# 08_BB_Processor.net
KiCad netlist of a schematic drawn in Altium Designer
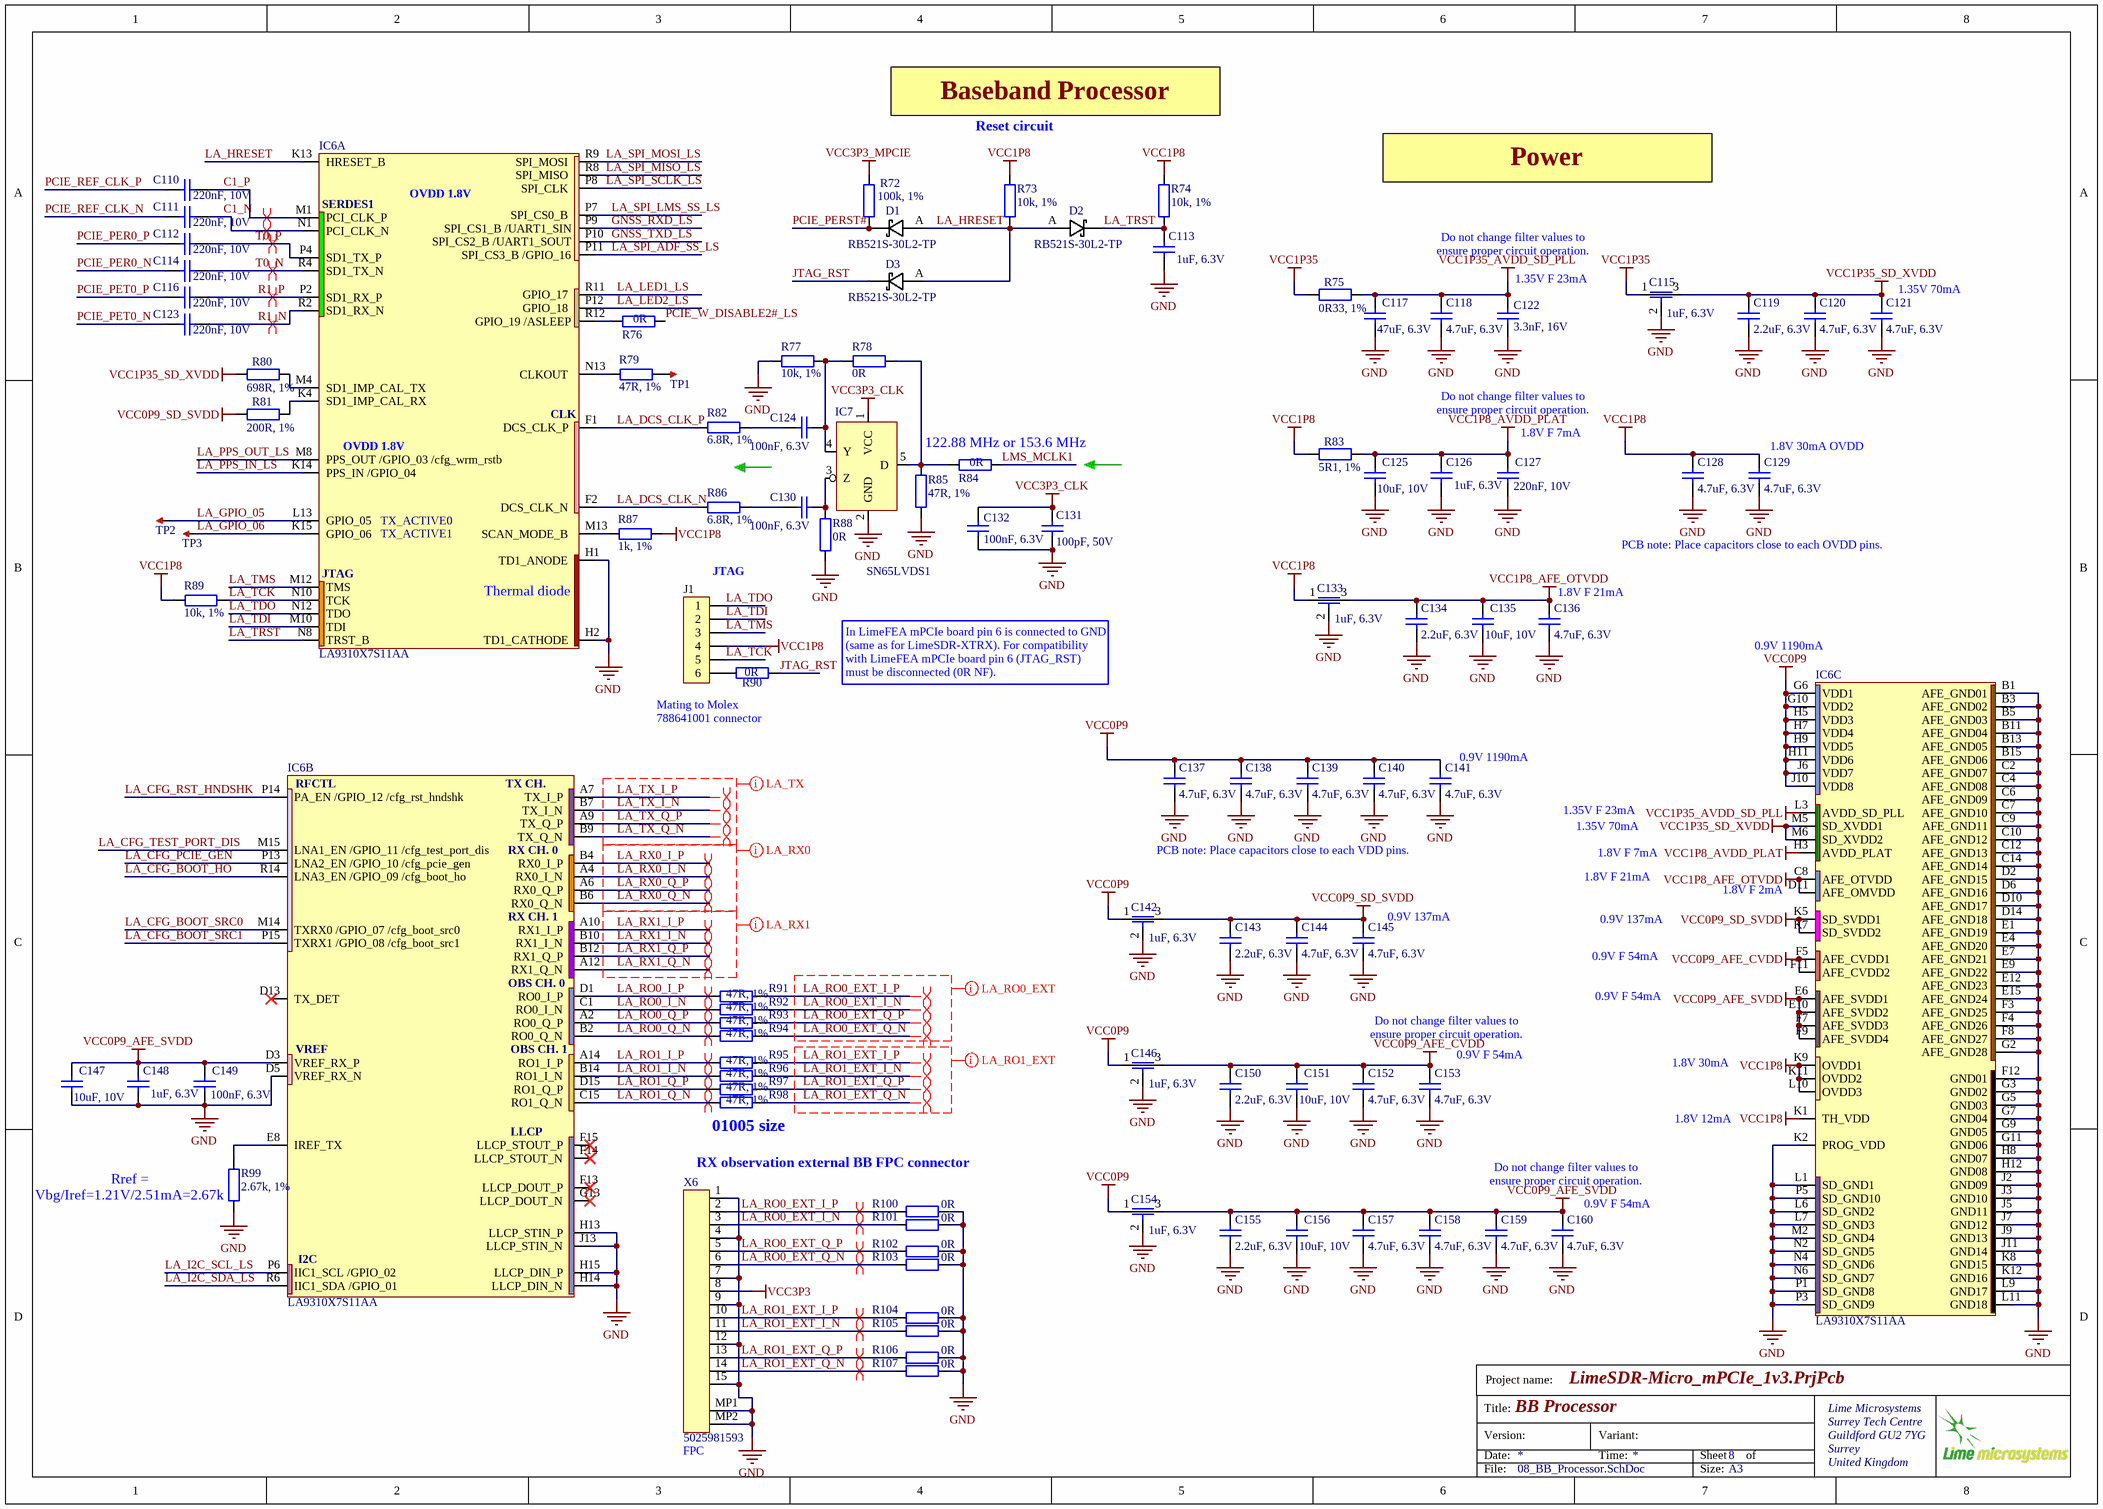
[diagram p0: 08_BB_Processor.SchDoc]

(export (version "E")
  (design (tool "Eeschema 10.0.6"))
  (components
    (comp (ref "C110")
      (value "220nF, 10V")
      (footprint "CAP0201")
      (fields
        (field (name "MANUFACTURER") "Murata")
        (field (name "TOLERANCE") "20%")
        (field (name "VOLTAGE") "10V")
      )
      (libsource (lib "LimeMicroAltiumLib_schLib") (part "Cap_0402"))
    )
    (comp (ref "C111")
      (value "220nF, 10V")
      (footprint "CAP0201")
      (fields
        (field (name "MANUFACTURER") "Murata")
        (field (name "TOLERANCE") "20%")
        (field (name "VOLTAGE") "10V")
      )
      (libsource (lib "LimeMicroAltiumLib_schLib") (part "Cap_0402"))
    )
    (comp (ref "C112")
      (value "220nF, 10V")
      (footprint "CAP0201")
      (fields
        (field (name "MANUFACTURER") "Murata")
        (field (name "TOLERANCE") "20%")
        (field (name "VOLTAGE") "10V")
      )
      (libsource (lib "LimeMicroAltiumLib_schLib") (part "Cap_0402"))
    )
    (comp (ref "C113")
      (value "1uF, 6.3V")
      (footprint "CAP0201")
      (fields (field (name "TOLERANCE") "±20%") (field (name "MANUFACTURER") "TDK Corporation"))
      (libsource (lib "LimeMicroAltiumLib_schLib") (part "Cap_0402"))
    )
    (comp (ref "C114")
      (value "220nF, 10V")
      (footprint "CAP0201")
      (fields
        (field (name "MANUFACTURER") "Murata")
        (field (name "TOLERANCE") "20%")
        (field (name "VOLTAGE") "10V")
      )
      (libsource (lib "LimeMicroAltiumLib_schLib") (part "Cap_0402"))
    )
    (comp (ref "C115")
      (value "1uF, 6.3V")
      (footprint "CAP0603_FEEDTHROUGH")
      (fields (field (name "MANUFACTURER") "TDK"))
      (libsource (lib "LimeMicroAltiumLib_schLib_r01") (part "Cap_feed_through"))
    )
    (comp (ref "C116")
      (value "220nF, 10V")
      (footprint "CAP0201")
      (fields
        (field (name "MANUFACTURER") "Murata")
        (field (name "TOLERANCE") "20%")
        (field (name "VOLTAGE") "10V")
      )
      (libsource (lib "LimeMicroAltiumLib_schLib") (part "Cap_0402"))
    )
    (comp (ref "C117")
      (value "47uF, 6.3V")
      (footprint "CAP0603")
      (fields (field (name "MANUFACTURER") "Murata") (field (name "TOLERANCE") "20%"))
      (libsource (lib "LimeFPGAboard_schLib") (part "Cap_0603"))
    )
    (comp (ref "C118")
      (value "4.7uF, 6.3V")
      (footprint "CAP0201")
      (fields (field (name "MANUFACTURER") "Murata") (field (name "TOLERANCE") "20%"))
      (libsource (lib "LimeMicroAltiumLib_schLib") (part "Cap_0402"))
    )
    (comp (ref "C119")
      (value "2.2uF, 6.3V")
      (footprint "CAP0201")
      (fields (field (name "MANUFACTURER") "Murata") (field (name "TOLERANCE") "20%"))
      (libsource (lib "LimeMicroAltiumLib_schLib") (part "Cap_0402"))
    )
    (comp (ref "C120")
      (value "4.7uF, 6.3V")
      (footprint "CAP0201")
      (fields (field (name "MANUFACTURER") "Murata") (field (name "TOLERANCE") "20%"))
      (libsource (lib "LimeMicroAltiumLib_schLib") (part "Cap_0402"))
    )
    (comp (ref "C121")
      (value "4.7uF, 6.3V")
      (footprint "CAP0201")
      (fields (field (name "MANUFACTURER") "Murata") (field (name "TOLERANCE") "20%"))
      (libsource (lib "LimeMicroAltiumLib_schLib") (part "Cap_0402"))
    )
    (comp (ref "C122")
      (value "3.3nF, 16V")
      (footprint "CAP0201")
      (fields (field (name "MANUFACTURER") "Murata"))
      (libsource (lib "LimeMicroAltiumLib_schLib") (part "Cap_0402"))
    )
    (comp (ref "C123")
      (value "220nF, 10V")
      (footprint "CAP0201")
      (fields
        (field (name "MANUFACTURER") "Murata")
        (field (name "TOLERANCE") "20%")
        (field (name "VOLTAGE") "10V")
      )
      (libsource (lib "LimeMicroAltiumLib_schLib") (part "Cap_0402"))
    )
    (comp (ref "C124")
      (value "100nF, 6.3V")
      (footprint "CAP0201")
      (fields (field (name "MANUFACTURER") "Samsung") (field (name "TOLERANCE") "20%"))
      (libsource (lib "LimeMicroAltiumLib_schLib") (part "Cap_0402"))
    )
    (comp (ref "C125")
      (value "10uF, 10V")
      (footprint "CAP0402")
      (fields (field (name "MANUFACTURER") "Murata"))
      (libsource (lib "LimeFPGAboard_schLib") (part "Cap_0603"))
    )
    (comp (ref "C126")
      (value "1uF, 6.3V")
      (footprint "CAP0201")
      (fields (field (name "TOLERANCE") "±20%") (field (name "MANUFACTURER") "TDK Corporation"))
      (libsource (lib "LimeMicroAltiumLib_schLib") (part "Cap_0402"))
    )
    (comp (ref "C127")
      (value "220nF, 10V")
      (footprint "CAP0201")
      (fields
        (field (name "MANUFACTURER") "Murata")
        (field (name "TOLERANCE") "20%")
        (field (name "VOLTAGE") "10V")
      )
      (libsource (lib "LimeMicroAltiumLib_schLib") (part "Cap_0402"))
    )
    (comp (ref "C128")
      (value "4.7uF, 6.3V")
      (footprint "CAP0201")
      (fields (field (name "MANUFACTURER") "Murata") (field (name "TOLERANCE") "20%"))
      (libsource (lib "LimeMicroAltiumLib_schLib") (part "Cap_0402"))
    )
    (comp (ref "C129")
      (value "4.7uF, 6.3V")
      (footprint "CAP0201")
      (fields (field (name "MANUFACTURER") "Murata") (field (name "TOLERANCE") "20%"))
      (libsource (lib "LimeMicroAltiumLib_schLib") (part "Cap_0402"))
    )
    (comp (ref "C130")
      (value "100nF, 6.3V")
      (footprint "CAP0201")
      (fields (field (name "MANUFACTURER") "Samsung") (field (name "TOLERANCE") "20%"))
      (libsource (lib "LimeMicroAltiumLib_schLib") (part "Cap_0402"))
    )
    (comp (ref "C131")
      (value "100pF, 50V")
      (footprint "CAP0201")
      (fields
        (field (name "MANUFACTURER") "TDK")
        (field (name "TOLERANCE") "5%")
        (field (name "VOLTAGE") "50V")
      )
      (libsource (lib "LimeMicroAltiumLib_schLib") (part "Cap_0402"))
    )
    (comp (ref "C132")
      (value "100nF, 6.3V")
      (footprint "CAP0201")
      (fields (field (name "MANUFACTURER") "Samsung") (field (name "TOLERANCE") "20%"))
      (libsource (lib "LimeMicroAltiumLib_schLib") (part "Cap_0402"))
    )
    (comp (ref "C133")
      (value "1uF, 6.3V")
      (footprint "CAP0603_FEEDTHROUGH")
      (fields (field (name "MANUFACTURER") "TDK"))
      (libsource (lib "LimeMicroAltiumLib_schLib_r01") (part "Cap_feed_through"))
    )
    (comp (ref "C134")
      (value "2.2uF, 6.3V")
      (footprint "CAP0201")
      (fields (field (name "MANUFACTURER") "Murata") (field (name "TOLERANCE") "20%"))
      (libsource (lib "LimeMicroAltiumLib_schLib") (part "Cap_0402"))
    )
    (comp (ref "C135")
      (value "10uF, 10V")
      (footprint "CAP0402")
      (fields (field (name "MANUFACTURER") "Murata"))
      (libsource (lib "LimeFPGAboard_schLib") (part "Cap_0603"))
    )
    (comp (ref "C136")
      (value "4.7uF, 6.3V")
      (footprint "CAP0201")
      (fields (field (name "MANUFACTURER") "Murata") (field (name "TOLERANCE") "20%"))
      (libsource (lib "LimeMicroAltiumLib_schLib") (part "Cap_0402"))
    )
    (comp (ref "C137")
      (value "4.7uF, 6.3V")
      (footprint "CAP0201")
      (fields (field (name "MANUFACTURER") "Murata") (field (name "TOLERANCE") "20%"))
      (libsource (lib "LimeMicroAltiumLib_schLib") (part "Cap_0402"))
    )
    (comp (ref "C138")
      (value "4.7uF, 6.3V")
      (footprint "CAP0201")
      (fields (field (name "MANUFACTURER") "Murata") (field (name "TOLERANCE") "20%"))
      (libsource (lib "LimeMicroAltiumLib_schLib") (part "Cap_0402"))
    )
    (comp (ref "C139")
      (value "4.7uF, 6.3V")
      (footprint "CAP0201")
      (fields (field (name "MANUFACTURER") "Murata") (field (name "TOLERANCE") "20%"))
      (libsource (lib "LimeMicroAltiumLib_schLib") (part "Cap_0402"))
    )
    (comp (ref "C140")
      (value "4.7uF, 6.3V")
      (footprint "CAP0201")
      (fields (field (name "MANUFACTURER") "Murata") (field (name "TOLERANCE") "20%"))
      (libsource (lib "LimeMicroAltiumLib_schLib") (part "Cap_0402"))
    )
    (comp (ref "C141")
      (value "4.7uF, 6.3V")
      (footprint "CAP0201")
      (fields (field (name "MANUFACTURER") "Murata") (field (name "TOLERANCE") "20%"))
      (libsource (lib "LimeMicroAltiumLib_schLib") (part "Cap_0402"))
    )
    (comp (ref "C142")
      (value "1uF, 6.3V")
      (footprint "CAP0603_FEEDTHROUGH")
      (fields (field (name "MANUFACTURER") "TDK"))
      (libsource (lib "LimeMicroAltiumLib_schLib_r01") (part "Cap_feed_through"))
    )
    (comp (ref "C143")
      (value "2.2uF, 6.3V")
      (footprint "CAP0201")
      (fields (field (name "MANUFACTURER") "Murata") (field (name "TOLERANCE") "20%"))
      (libsource (lib "LimeMicroAltiumLib_schLib") (part "Cap_0402"))
    )
    (comp (ref "C144")
      (value "4.7uF, 6.3V")
      (footprint "CAP0201")
      (fields (field (name "MANUFACTURER") "Murata") (field (name "TOLERANCE") "20%"))
      (libsource (lib "LimeMicroAltiumLib_schLib") (part "Cap_0402"))
    )
    (comp (ref "C145")
      (value "4.7uF, 6.3V")
      (footprint "CAP0201")
      (fields (field (name "MANUFACTURER") "Murata") (field (name "TOLERANCE") "20%"))
      (libsource (lib "LimeMicroAltiumLib_schLib") (part "Cap_0402"))
    )
    (comp (ref "C146")
      (value "1uF, 6.3V")
      (footprint "CAP0603_FEEDTHROUGH")
      (fields (field (name "MANUFACTURER") "TDK"))
      (libsource (lib "LimeMicroAltiumLib_schLib_r01") (part "Cap_feed_through"))
    )
    (comp (ref "C147")
      (value "10uF, 10V")
      (footprint "CAP0402")
      (fields (field (name "MANUFACTURER") "Murata"))
      (libsource (lib "LimeFPGAboard_schLib") (part "Cap_0603"))
    )
    (comp (ref "C148")
      (value "1uF, 6.3V")
      (footprint "CAP0201")
      (fields (field (name "TOLERANCE") "±20%") (field (name "MANUFACTURER") "TDK Corporation"))
      (libsource (lib "LimeMicroAltiumLib_schLib") (part "Cap_0402"))
    )
    (comp (ref "C149")
      (value "100nF, 6.3V")
      (footprint "CAP0201")
      (fields (field (name "MANUFACTURER") "Samsung") (field (name "TOLERANCE") "20%"))
      (libsource (lib "LimeMicroAltiumLib_schLib") (part "Cap_0402"))
    )
    (comp (ref "C150")
      (value "2.2uF, 6.3V")
      (footprint "CAP0201")
      (fields (field (name "MANUFACTURER") "Murata") (field (name "TOLERANCE") "20%"))
      (libsource (lib "LimeMicroAltiumLib_schLib") (part "Cap_0402"))
    )
    (comp (ref "C151")
      (value "10uF, 10V")
      (footprint "CAP0402")
      (fields (field (name "MANUFACTURER") "Murata"))
      (libsource (lib "LimeFPGAboard_schLib") (part "Cap_0603"))
    )
    (comp (ref "C152")
      (value "4.7uF, 6.3V")
      (footprint "CAP0201")
      (fields (field (name "MANUFACTURER") "Murata") (field (name "TOLERANCE") "20%"))
      (libsource (lib "LimeMicroAltiumLib_schLib") (part "Cap_0402"))
    )
    (comp (ref "C153")
      (value "4.7uF, 6.3V")
      (footprint "CAP0201")
      (fields (field (name "MANUFACTURER") "Murata") (field (name "TOLERANCE") "20%"))
      (libsource (lib "LimeMicroAltiumLib_schLib") (part "Cap_0402"))
    )
    (comp (ref "C154")
      (value "1uF, 6.3V")
      (footprint "CAP0603_FEEDTHROUGH")
      (fields (field (name "MANUFACTURER") "TDK"))
      (libsource (lib "LimeMicroAltiumLib_schLib_r01") (part "Cap_feed_through"))
    )
    (comp (ref "C155")
      (value "2.2uF, 6.3V")
      (footprint "CAP0201")
      (fields (field (name "MANUFACTURER") "Murata") (field (name "TOLERANCE") "20%"))
      (libsource (lib "LimeMicroAltiumLib_schLib") (part "Cap_0402"))
    )
    (comp (ref "C156")
      (value "10uF, 10V")
      (footprint "CAP0402")
      (fields (field (name "MANUFACTURER") "Murata"))
      (libsource (lib "LimeFPGAboard_schLib") (part "Cap_0603"))
    )
    (comp (ref "C157")
      (value "4.7uF, 6.3V")
      (footprint "CAP0201")
      (fields (field (name "MANUFACTURER") "Murata") (field (name "TOLERANCE") "20%"))
      (libsource (lib "LimeMicroAltiumLib_schLib") (part "Cap_0402"))
    )
    (comp (ref "C158")
      (value "4.7uF, 6.3V")
      (footprint "CAP0201")
      (fields (field (name "MANUFACTURER") "Murata") (field (name "TOLERANCE") "20%"))
      (libsource (lib "LimeMicroAltiumLib_schLib") (part "Cap_0402"))
    )
    (comp (ref "C159")
      (value "4.7uF, 6.3V")
      (footprint "CAP0201")
      (fields (field (name "MANUFACTURER") "Murata") (field (name "TOLERANCE") "20%"))
      (libsource (lib "LimeMicroAltiumLib_schLib") (part "Cap_0402"))
    )
    (comp (ref "C160")
      (value "4.7uF, 6.3V")
      (footprint "CAP0201")
      (fields (field (name "MANUFACTURER") "Murata") (field (name "TOLERANCE") "20%"))
      (libsource (lib "LimeMicroAltiumLib_schLib") (part "Cap_0402"))
    )
    (comp (ref "D1")
      (value "RB521S-30L2-TP")
      (footprint "RB521S-30L2-TP_DFN1006")
      (fields (field (name "MANUFACTURER") "MCC"))
      (libsource (lib "LimeMicroAltiumLib") (part "BAT46JFILM_shottky_diode"))
    )
    (comp (ref "D2")
      (value "RB521S-30L2-TP")
      (footprint "RB521S-30L2-TP_DFN1006")
      (fields (field (name "MANUFACTURER") "MCC"))
      (libsource (lib "LimeMicroAltiumLib") (part "BAT46JFILM_shottky_diode"))
    )
    (comp (ref "D3")
      (value "RB521S-30L2-TP")
      (footprint "RB521S-30L2-TP_DFN1006")
      (fields (field (name "MANUFACTURER") "MCC"))
      (libsource (lib "LimeMicroAltiumLib") (part "BAT46JFILM_shottky_diode"))
    )
    (comp (ref "IC6")
      (value "LA9310X7S11AA")
      (footprint "LA9310X7S11AA")
      (fields (field (name "MANUFACTURER") "NXP Semiconductors"))
      (libsource (lib "LimeMicroAltiumLib") (part "LA9310X7S11AA"))
    )
    (comp (ref "IC7")
      (value "SN65LVDS1")
      (footprint "SOT23-5_NO_SILK")
      (fields (field (name "MANUFACTURER") "TEXAS INSTRUMENTS"))
      (libsource (lib "LimeMicroAltiumLib_schLib") (part "SN65LVDS1"))
    )
    (comp (ref "J1")
      (value "Molex 0788641001")
      (footprint "Molex_0788641001_spring_contacts")
      (description "Header, 6-pin")
      (fields (field (name "MANUFACTURER") "Molex"))
      (libsource (lib "LimeMicroAltiumLib_schLib_r04") (part "Molex_0788641001_spring_contacts"))
    )
    (comp (ref "R72")
      (value "100k, 1%")
      (footprint "RES0201")
      (fields (field (name "MANUFACTURER") "Yageo") (field (name "TOLERANCE") "1%"))
      (libsource (lib "LimeFPGAboard_schLib") (part "Res_0402"))
    )
    (comp (ref "R73")
      (value "10k, 1%")
      (footprint "RES0201")
      (fields (field (name "MANUFACTURER") "Yageo") (field (name "TOLERANCE") "1%"))
      (libsource (lib "LimeFPGAboard_schLib") (part "Res_0402"))
    )
    (comp (ref "R74")
      (value "10k, 1%")
      (footprint "RES0201")
      (fields (field (name "MANUFACTURER") "Yageo") (field (name "TOLERANCE") "1%"))
      (libsource (lib "LimeFPGAboard_schLib") (part "Res_0402"))
    )
    (comp (ref "R75")
      (value "0R33, 1%")
      (footprint "RES0201")
      (fields (field (name "MANUFACTURER") "Ohmite"))
      (libsource (lib "LimeFPGAboard_schLib") (part "Res_0402"))
    )
    (comp (ref "R76")
      (value "0R")
      (footprint "RES0201")
      (fields (field (name "MANUFACTURER") "Yageo") (field (name "TOLERANCE") "5%"))
      (libsource (lib "LimeFPGAboard_schLib") (part "Res_0402"))
    )
    (comp (ref "R77")
      (value "10k, 1%")
      (footprint "RES0201")
      (fields (field (name "MANUFACTURER") "Yageo") (field (name "TOLERANCE") "1%"))
      (libsource (lib "LimeFPGAboard_schLib") (part "Res_0402"))
    )
    (comp (ref "R78")
      (value "0R")
      (footprint "RES0201")
      (fields (field (name "MANUFACTURER") "Yageo") (field (name "TOLERANCE") "5%"))
      (libsource (lib "LimeFPGAboard_schLib") (part "Res_0402"))
    )
    (comp (ref "R79")
      (value "47R, 1%")
      (footprint "RES0201")
      (fields (field (name "MANUFACTURER") "Yageo") (field (name "TOLERANCE") "1%"))
      (libsource (lib "LimeFPGAboard_schLib") (part "Res_0402"))
    )
    (comp (ref "R80")
      (value "698R, 1%")
      (footprint "RES0201")
      (fields (field (name "MANUFACTURER") "Yageo") (field (name "TOLERANCE") "1%"))
      (libsource (lib "LimeFPGAboard_schLib") (part "Res_0402"))
    )
    (comp (ref "R81")
      (value "200R, 1%")
      (footprint "RES0201")
      (fields (field (name "MANUFACTURER") "Yageo") (field (name "TOLERANCE") "1%"))
      (libsource (lib "LimeFPGAboard_schLib") (part "Res_0402"))
    )
    (comp (ref "R82")
      (value "6.8R, 1%")
      (footprint "RES0201")
      (fields (field (name "MANUFACTURER") "Yageo") (field (name "TOLERANCE") "1%"))
      (libsource (lib "LimeMicroAltiumLib_schLib") (part "Res_0402"))
    )
    (comp (ref "R83")
      (value "5R1, 1%")
      (footprint "RES0201")
      (fields (field (name "MANUFACTURER") "Yageo"))
      (libsource (lib "LimeFPGAboard_schLib") (part "Res_0402"))
    )
    (comp (ref "R84")
      (value "0R")
      (footprint "RES0201")
      (fields (field (name "MANUFACTURER") "Yageo") (field (name "TOLERANCE") "5%"))
      (libsource (lib "LimeFPGAboard_schLib") (part "Res_0402"))
    )
    (comp (ref "R85")
      (value "47R, 1%")
      (footprint "RES0201")
      (fields (field (name "MANUFACTURER") "Yageo") (field (name "TOLERANCE") "1%"))
      (libsource (lib "LimeFPGAboard_schLib") (part "Res_0402"))
    )
    (comp (ref "R86")
      (value "6.8R, 1%")
      (footprint "RES0201")
      (fields (field (name "MANUFACTURER") "Yageo") (field (name "TOLERANCE") "1%"))
      (libsource (lib "LimeMicroAltiumLib_schLib") (part "Res_0402"))
    )
    (comp (ref "R87")
      (value "1k, 1%")
      (footprint "RES0201")
      (fields (field (name "MANUFACTURER") "Yageo") (field (name "TOLERANCE") "1%"))
      (libsource (lib "LimeMicroAltiumLib_schLib") (part "Res_0402"))
    )
    (comp (ref "R88")
      (value "0R")
      (footprint "RES0201")
      (fields (field (name "MANUFACTURER") "Yageo") (field (name "TOLERANCE") "5%"))
      (libsource (lib "LimeFPGAboard_schLib") (part "Res_0402"))
    )
    (comp (ref "R89")
      (value "10k, 1%")
      (footprint "RES0201")
      (fields (field (name "MANUFACTURER") "Yageo") (field (name "TOLERANCE") "1%"))
      (libsource (lib "LimeFPGAboard_schLib") (part "Res_0402"))
    )
    (comp (ref "R90")
      (value "0R")
      (footprint "RES0201")
      (fields (field (name "MANUFACTURER") "Yageo") (field (name "TOLERANCE") "5%"))
      (libsource (lib "LimeFPGAboard_schLib") (part "Res_0402"))
    )
    (comp (ref "R91")
      (value "47R, 1%")
      (footprint "RES01005")
      (fields (field (name "MANUFACTURER") "Yageo") (field (name "TOLERANCE") "1%"))
      (libsource (lib "LimeFPGAboard_schLib") (part "Res_0402"))
    )
    (comp (ref "R92")
      (value "47R, 1%")
      (footprint "RES01005")
      (fields (field (name "MANUFACTURER") "Yageo") (field (name "TOLERANCE") "1%"))
      (libsource (lib "LimeFPGAboard_schLib") (part "Res_0402"))
    )
    (comp (ref "R93")
      (value "47R, 1%")
      (footprint "RES01005")
      (fields (field (name "MANUFACTURER") "Yageo") (field (name "TOLERANCE") "1%"))
      (libsource (lib "LimeFPGAboard_schLib") (part "Res_0402"))
    )
    (comp (ref "R94")
      (value "47R, 1%")
      (footprint "RES01005")
      (fields (field (name "MANUFACTURER") "Yageo") (field (name "TOLERANCE") "1%"))
      (libsource (lib "LimeFPGAboard_schLib") (part "Res_0402"))
    )
    (comp (ref "R95")
      (value "47R, 1%")
      (footprint "RES01005")
      (fields (field (name "MANUFACTURER") "Yageo") (field (name "TOLERANCE") "1%"))
      (libsource (lib "LimeFPGAboard_schLib") (part "Res_0402"))
    )
    (comp (ref "R96")
      (value "47R, 1%")
      (footprint "RES01005")
      (fields (field (name "MANUFACTURER") "Yageo") (field (name "TOLERANCE") "1%"))
      (libsource (lib "LimeFPGAboard_schLib") (part "Res_0402"))
    )
    (comp (ref "R97")
      (value "47R, 1%")
      (footprint "RES01005")
      (fields (field (name "MANUFACTURER") "Yageo") (field (name "TOLERANCE") "1%"))
      (libsource (lib "LimeFPGAboard_schLib") (part "Res_0402"))
    )
    (comp (ref "R98")
      (value "47R, 1%")
      (footprint "RES01005")
      (fields (field (name "MANUFACTURER") "Yageo") (field (name "TOLERANCE") "1%"))
      (libsource (lib "LimeFPGAboard_schLib") (part "Res_0402"))
    )
    (comp (ref "R99")
      (value "2.67k, 1%")
      (footprint "RES0201")
      (fields (field (name "MANUFACTURER") "Stackpole Electronics") (field (name "TOLERANCE") "1%"))
      (libsource (lib "LimeFPGAboard_schLib") (part "Res_0402"))
    )
    (comp (ref "R100")
      (value "0R")
      (footprint "RES01005")
      (fields (field (name "MANUFACTURER") "Panasonic") (field (name "TOLERANCE") "5%"))
      (libsource (lib "LimeFPGAboard_schLib") (part "Res_0402"))
    )
    (comp (ref "R101")
      (value "0R")
      (footprint "RES01005")
      (fields (field (name "MANUFACTURER") "Panasonic") (field (name "TOLERANCE") "5%"))
      (libsource (lib "LimeFPGAboard_schLib") (part "Res_0402"))
    )
    (comp (ref "R102")
      (value "0R")
      (footprint "RES01005")
      (fields (field (name "MANUFACTURER") "Panasonic") (field (name "TOLERANCE") "5%"))
      (libsource (lib "LimeFPGAboard_schLib") (part "Res_0402"))
    )
    (comp (ref "R103")
      (value "0R")
      (footprint "RES01005")
      (fields (field (name "MANUFACTURER") "Panasonic") (field (name "TOLERANCE") "5%"))
      (libsource (lib "LimeFPGAboard_schLib") (part "Res_0402"))
    )
    (comp (ref "R104")
      (value "0R")
      (footprint "RES01005")
      (fields (field (name "MANUFACTURER") "Panasonic") (field (name "TOLERANCE") "5%"))
      (libsource (lib "LimeFPGAboard_schLib") (part "Res_0402"))
    )
    (comp (ref "R105")
      (value "0R")
      (footprint "RES01005")
      (fields (field (name "MANUFACTURER") "Panasonic") (field (name "TOLERANCE") "5%"))
      (libsource (lib "LimeFPGAboard_schLib") (part "Res_0402"))
    )
    (comp (ref "R106")
      (value "0R")
      (footprint "RES01005")
      (fields (field (name "MANUFACTURER") "Panasonic") (field (name "TOLERANCE") "5%"))
      (libsource (lib "LimeFPGAboard_schLib") (part "Res_0402"))
    )
    (comp (ref "R107")
      (value "0R")
      (footprint "RES01005")
      (fields (field (name "MANUFACTURER") "Panasonic") (field (name "TOLERANCE") "5%"))
      (libsource (lib "LimeFPGAboard_schLib") (part "Res_0402"))
    )
    (comp (ref "TP1")
      (value "TESTPOINT_PAD")
      (footprint "TP_PAD_1MM")
      (description "Test Point PCB mount Miniature White")
      (libsource (lib "LimeMicroAltiumLib_schLib_r04") (part "TESTPOINT_PAD"))
    )
    (comp (ref "TP2")
      (value "TESTPOINT_PAD")
      (footprint "TP_PAD_1MM")
      (description "Test Point PCB mount Miniature White")
      (libsource (lib "LimeMicroAltiumLib_schLib_r04") (part "TESTPOINT_PAD"))
    )
    (comp (ref "TP3")
      (value "TESTPOINT_PAD")
      (footprint "TP_PAD_1MM")
      (description "Test Point PCB mount Miniature White")
      (libsource (lib "LimeMicroAltiumLib_schLib_r04") (part "TESTPOINT_PAD"))
    )
    (comp (ref "X6")
      (value "5025981593")
      (footprint "5025981593_FPC_connector")
      (fields (field (name "MANUFACTURER") "Molex"))
      (libsource (lib "LimeMicroAltiumLib_schLib_r04") (part "5025981593_FPC_connector"))
    )
  )
  (nets
    (net (code "1") (name "/C1_N") (class "Default")
      (node (ref "C111") (pin "2") (pinfunction "2_2") (pintype "passive"))
      (node (ref "IC6") (pin "N1") (pinfunction "PCI_CLK_N_N1") (pintype "power_in"))
    )
    (net (code "2") (name "/C1_P") (class "Default")
      (node (ref "C110") (pin "2") (pinfunction "2_2") (pintype "passive"))
      (node (ref "IC6") (pin "M1") (pinfunction "PCI_CLK_P_M1") (pintype "power_in"))
    )
    (net (code "3") (name "/GNSS_RXD_LS") (class "Default")
      (node (ref "IC6") (pin "P9") (pinfunction "SPI_CS1_B_/UART1_SIN_P9") (pintype "power_in"))
    )
    (net (code "4") (name "/GNSS_TXD_LS") (class "Default")
      (node (ref "IC6") (pin "P10") (pinfunction "SPI_CS2_B_/UART1_SOUT_P10") (pintype "power_in"))
    )
    (net (code "5") (name "/JTAG_RST") (class "Default")
      (node (ref "D3") (pin "C") (pinfunction "C_C") (pintype "passive"))
      (node (ref "R90") (pin "2") (pinfunction "2_2") (pintype "passive"))
    )
    (net (code "6") (name "/LA_CFG_BOOT_HO") (class "Default")
      (node (ref "IC6") (pin "R14") (pinfunction "LNA3_EN_/GPIO_09_/cfg_boot_ho_R14") (pintype "power_in"))
    )
    (net (code "7") (name "/LA_CFG_BOOT_SRC0") (class "Default")
      (node (ref "IC6") (pin "M14") (pinfunction "TXRX0_/GPIO_07_/cfg_boot_src0_M14") (pintype "power_in"))
    )
    (net (code "8") (name "/LA_CFG_BOOT_SRC1") (class "Default")
      (node (ref "IC6") (pin "P15") (pinfunction "TXRX1_/GPIO_08_/cfg_boot_src1_P15") (pintype "power_in"))
    )
    (net (code "9") (name "/LA_CFG_PCIE_GEN") (class "Default")
      (node (ref "IC6") (pin "P13") (pinfunction "LNA2_EN_/GPIO_10_/cfg_pcie_gen_P13") (pintype "power_in"))
    )
    (net (code "10") (name "/LA_CFG_RST_HNDSHK") (class "Default")
      (node (ref "IC6") (pin "P14") (pinfunction "PA_EN_/GPIO_12_/cfg_rst_hndshk_P14") (pintype "power_in"))
    )
    (net (code "11") (name "/LA_CFG_TEST_PORT_DIS") (class "Default")
      (node (ref "IC6") (pin "M15") (pinfunction "LNA1_EN_/GPIO_11_/cfg_test_port_dis_M15") (pintype "power_in"))
    )
    (net (code "12") (name "/LA_DCS_CLK_N") (class "Default")
      (node (ref "IC6") (pin "F2") (pinfunction "DCS_CLK_N_F2") (pintype "power_in"))
      (node (ref "R86") (pin "2") (pinfunction "2_2") (pintype "passive"))
    )
    (net (code "13") (name "/LA_DCS_CLK_P") (class "Default")
      (node (ref "IC6") (pin "F1") (pinfunction "DCS_CLK_P_F1") (pintype "power_in"))
      (node (ref "R82") (pin "2") (pinfunction "2_2") (pintype "passive"))
    )
    (net (code "14") (name "/LA_GPIO_05") (class "Default")
      (node (ref "IC6") (pin "L13") (pinfunction "GPIO_05_L13") (pintype "power_in"))
      (node (ref "TP2") (pin "1") (pintype "passive"))
    )
    (net (code "15") (name "/LA_GPIO_06") (class "Default")
      (node (ref "IC6") (pin "K15") (pinfunction "GPIO_06_K15") (pintype "power_in"))
      (node (ref "TP3") (pin "1") (pintype "passive"))
    )
    (net (code "16") (name "/LA_HRESET") (class "Default")
      (node (ref "D1") (pin "A") (pinfunction "A_A") (pintype "passive"))
      (node (ref "D2") (pin "A") (pinfunction "A_A") (pintype "passive"))
      (node (ref "D3") (pin "A") (pinfunction "A_A") (pintype "passive"))
      (node (ref "IC6") (pin "K13") (pinfunction "HRESET_B_K13") (pintype "power_in"))
      (node (ref "R73") (pin "2") (pinfunction "2_2") (pintype "passive"))
    )
    (net (code "17") (name "/LA_I2C_SCL_LS") (class "Default")
      (node (ref "IC6") (pin "P6") (pinfunction "IIC1_SCL_/GPIO_02_P6") (pintype "power_in"))
    )
    (net (code "18") (name "/LA_I2C_SDA_LS") (class "Default")
      (node (ref "IC6") (pin "R6") (pinfunction "IIC1_SDA_/GPIO_01_R6") (pintype "power_in"))
    )
    (net (code "19") (name "/LA_LED1_LS") (class "Default")
      (node (ref "IC6") (pin "R11") (pinfunction "GPIO_17_R11") (pintype "power_in"))
    )
    (net (code "20") (name "/LA_LED2_LS") (class "Default")
      (node (ref "IC6") (pin "P12") (pinfunction "GPIO_18_P12") (pintype "power_in"))
    )
    (net (code "21") (name "/LA_PPS_IN_LS") (class "Default")
      (node (ref "IC6") (pin "K14") (pinfunction "PPS_IN_/GPIO_04_K14") (pintype "power_in"))
    )
    (net (code "22") (name "/LA_PPS_OUT_LS") (class "Default")
      (node (ref "IC6") (pin "M8") (pinfunction "PPS_OUT_/GPIO_03_/cfg_wrm_rstb_M8") (pintype "power_in"))
    )
    (net (code "23") (name "/LA_RO0_EXT_I_N") (class "Default")
      (node (ref "R101") (pin "1") (pinfunction "1_1") (pintype "passive"))
      (node (ref "R92") (pin "2") (pinfunction "2_2") (pintype "passive"))
      (node (ref "X6") (pin "3") (pinfunction "3_3") (pintype "passive"))
    )
    (net (code "24") (name "/LA_RO0_EXT_I_P") (class "Default")
      (node (ref "R100") (pin "1") (pinfunction "1_1") (pintype "passive"))
      (node (ref "R91") (pin "2") (pinfunction "2_2") (pintype "passive"))
      (node (ref "X6") (pin "2") (pinfunction "2_2") (pintype "passive"))
    )
    (net (code "25") (name "/LA_RO0_EXT_Q_N") (class "Default")
      (node (ref "R103") (pin "1") (pinfunction "1_1") (pintype "passive"))
      (node (ref "R94") (pin "2") (pinfunction "2_2") (pintype "passive"))
      (node (ref "X6") (pin "6") (pinfunction "6_6") (pintype "passive"))
    )
    (net (code "26") (name "/LA_RO0_EXT_Q_P") (class "Default")
      (node (ref "R102") (pin "1") (pinfunction "1_1") (pintype "passive"))
      (node (ref "R93") (pin "2") (pinfunction "2_2") (pintype "passive"))
      (node (ref "X6") (pin "5") (pinfunction "5_5") (pintype "passive"))
    )
    (net (code "27") (name "/LA_RO0_I_N") (class "Default")
      (node (ref "IC6") (pin "C1") (pinfunction "RO0_I_N_C1") (pintype "power_in"))
      (node (ref "R92") (pin "1") (pinfunction "1_1") (pintype "passive"))
    )
    (net (code "28") (name "/LA_RO0_I_P") (class "Default")
      (node (ref "IC6") (pin "D1") (pinfunction "RO0_I_P_D1") (pintype "power_in"))
      (node (ref "R91") (pin "1") (pinfunction "1_1") (pintype "passive"))
    )
    (net (code "29") (name "/LA_RO0_Q_N") (class "Default")
      (node (ref "IC6") (pin "B2") (pinfunction "RO0_Q_N_B2") (pintype "power_in"))
      (node (ref "R94") (pin "1") (pinfunction "1_1") (pintype "passive"))
    )
    (net (code "30") (name "/LA_RO0_Q_P") (class "Default")
      (node (ref "IC6") (pin "A2") (pinfunction "RO0_Q_P_A2") (pintype "power_in"))
      (node (ref "R93") (pin "1") (pinfunction "1_1") (pintype "passive"))
    )
    (net (code "31") (name "/LA_RO1_EXT_I_N") (class "Default")
      (node (ref "R105") (pin "1") (pinfunction "1_1") (pintype "passive"))
      (node (ref "R96") (pin "2") (pinfunction "2_2") (pintype "passive"))
      (node (ref "X6") (pin "11") (pinfunction "11_11") (pintype "passive"))
    )
    (net (code "32") (name "/LA_RO1_EXT_I_P") (class "Default")
      (node (ref "R104") (pin "1") (pinfunction "1_1") (pintype "passive"))
      (node (ref "R95") (pin "2") (pinfunction "2_2") (pintype "passive"))
      (node (ref "X6") (pin "10") (pinfunction "10_10") (pintype "passive"))
    )
    (net (code "33") (name "/LA_RO1_EXT_Q_N") (class "Default")
      (node (ref "R107") (pin "1") (pinfunction "1_1") (pintype "passive"))
      (node (ref "R98") (pin "2") (pinfunction "2_2") (pintype "passive"))
      (node (ref "X6") (pin "14") (pinfunction "14_14") (pintype "passive"))
    )
    (net (code "34") (name "/LA_RO1_EXT_Q_P") (class "Default")
      (node (ref "R106") (pin "1") (pinfunction "1_1") (pintype "passive"))
      (node (ref "R97") (pin "2") (pinfunction "2_2") (pintype "passive"))
      (node (ref "X6") (pin "13") (pinfunction "13_13") (pintype "passive"))
    )
    (net (code "35") (name "/LA_RO1_I_N") (class "Default")
      (node (ref "IC6") (pin "B14") (pinfunction "RO1_I_N_B14") (pintype "power_in"))
      (node (ref "R96") (pin "1") (pinfunction "1_1") (pintype "passive"))
    )
    (net (code "36") (name "/LA_RO1_I_P") (class "Default")
      (node (ref "IC6") (pin "A14") (pinfunction "RO1_I_P_A14") (pintype "power_in"))
      (node (ref "R95") (pin "1") (pinfunction "1_1") (pintype "passive"))
    )
    (net (code "37") (name "/LA_RO1_Q_N") (class "Default")
      (node (ref "IC6") (pin "C15") (pinfunction "RO1_Q_N_C15") (pintype "power_in"))
      (node (ref "R98") (pin "1") (pinfunction "1_1") (pintype "passive"))
    )
    (net (code "38") (name "/LA_RO1_Q_P") (class "Default")
      (node (ref "IC6") (pin "D15") (pinfunction "RO1_Q_P_D15") (pintype "power_in"))
      (node (ref "R97") (pin "1") (pinfunction "1_1") (pintype "passive"))
    )
    (net (code "39") (name "/LA_RX0_I_N") (class "Default")
      (node (ref "IC6") (pin "A4") (pinfunction "RX0_I_N_A4") (pintype "power_in"))
    )
    (net (code "40") (name "/LA_RX0_I_P") (class "Default")
      (node (ref "IC6") (pin "B4") (pinfunction "RX0_I_P_B4") (pintype "power_in"))
    )
    (net (code "41") (name "/LA_RX0_Q_N") (class "Default")
      (node (ref "IC6") (pin "B6") (pinfunction "RX0_Q_N_B6") (pintype "power_in"))
    )
    (net (code "42") (name "/LA_RX0_Q_P") (class "Default")
      (node (ref "IC6") (pin "A6") (pinfunction "RX0_Q_P_A6") (pintype "power_in"))
    )
    (net (code "43") (name "/LA_RX1_I_N") (class "Default")
      (node (ref "IC6") (pin "B10") (pinfunction "RX1_I_N_B10") (pintype "power_in"))
    )
    (net (code "44") (name "/LA_RX1_I_P") (class "Default")
      (node (ref "IC6") (pin "A10") (pinfunction "RX1_I_P_A10") (pintype "power_in"))
    )
    (net (code "45") (name "/LA_RX1_Q_N") (class "Default")
      (node (ref "IC6") (pin "A12") (pinfunction "RX1_Q_N_A12") (pintype "power_in"))
    )
    (net (code "46") (name "/LA_RX1_Q_P") (class "Default")
      (node (ref "IC6") (pin "B12") (pinfunction "RX1_Q_P_B12") (pintype "power_in"))
    )
    (net (code "47") (name "/LA_SPI_ADF_SS_LS") (class "Default")
      (node (ref "IC6") (pin "P11") (pinfunction "SPI_CS3_B_/GPIO_16_P11") (pintype "power_in"))
    )
    (net (code "48") (name "/LA_SPI_LMS_SS_LS") (class "Default")
      (node (ref "IC6") (pin "P7") (pinfunction "SPI_CS0_B_P7") (pintype "power_in"))
    )
    (net (code "49") (name "/LA_SPI_MISO_LS") (class "Default")
      (node (ref "IC6") (pin "R8") (pinfunction "SPI_MISO_R8") (pintype "power_in"))
    )
    (net (code "50") (name "/LA_SPI_MOSI_LS") (class "Default")
      (node (ref "IC6") (pin "R9") (pinfunction "SPI_MOSI_R9") (pintype "power_in"))
    )
    (net (code "51") (name "/LA_SPI_SCLK_LS") (class "Default")
      (node (ref "IC6") (pin "P8") (pinfunction "SPI_CLK_P8") (pintype "power_in"))
    )
    (net (code "52") (name "/LA_TCK") (class "Default")
      (node (ref "IC6") (pin "N10") (pinfunction "TCK_N10") (pintype "power_in"))
      (node (ref "J1") (pin "5") (pinfunction "5_5") (pintype "passive"))
      (node (ref "R89") (pin "2") (pinfunction "2_2") (pintype "passive"))
    )
    (net (code "53") (name "/LA_TDI") (class "Default")
      (node (ref "IC6") (pin "M10") (pinfunction "TDI_M10") (pintype "power_in"))
      (node (ref "J1") (pin "2") (pinfunction "2_2") (pintype "passive"))
    )
    (net (code "54") (name "/LA_TDO") (class "Default")
      (node (ref "IC6") (pin "N12") (pinfunction "TDO_N12") (pintype "power_in"))
      (node (ref "J1") (pin "1") (pinfunction "1_1") (pintype "passive"))
    )
    (net (code "55") (name "/LA_TMS") (class "Default")
      (node (ref "IC6") (pin "M12") (pinfunction "TMS_M12") (pintype "power_in"))
      (node (ref "J1") (pin "3") (pinfunction "3_3") (pintype "passive"))
    )
    (net (code "56") (name "/LA_TRST") (class "Default")
      (node (ref "C113") (pin "1") (pinfunction "1_1") (pintype "passive"))
      (node (ref "D2") (pin "C") (pinfunction "C_C") (pintype "passive"))
      (node (ref "IC6") (pin "N8") (pinfunction "TRST_B_N8") (pintype "power_in"))
      (node (ref "R74") (pin "2") (pinfunction "2_2") (pintype "passive"))
    )
    (net (code "57") (name "/LA_TX_I_N") (class "Default")
      (node (ref "IC6") (pin "B7") (pinfunction "TX_I_N_B7") (pintype "power_in"))
    )
    (net (code "58") (name "/LA_TX_I_P") (class "Default")
      (node (ref "IC6") (pin "A7") (pinfunction "TX_I_P_A7") (pintype "power_in"))
    )
    (net (code "59") (name "/LA_TX_Q_N") (class "Default")
      (node (ref "IC6") (pin "B9") (pinfunction "TX_Q_N_B9") (pintype "power_in"))
    )
    (net (code "60") (name "/LA_TX_Q_P") (class "Default")
      (node (ref "IC6") (pin "A9") (pinfunction "TX_Q_P_A9") (pintype "power_in"))
    )
    (net (code "61") (name "/LMS_MCLK1") (class "Default")
      (node (ref "R84") (pin "1") (pinfunction "1_1") (pintype "passive"))
    )
    (net (code "62") (name "/PCIE_PER0_N") (class "Default")
      (node (ref "C114") (pin "1") (pinfunction "1_1") (pintype "passive"))
    )
    (net (code "63") (name "/PCIE_PER0_P") (class "Default")
      (node (ref "C112") (pin "1") (pinfunction "1_1") (pintype "passive"))
    )
    (net (code "64") (name "/PCIE_PERST#") (class "Default")
      (node (ref "D1") (pin "C") (pinfunction "C_C") (pintype "passive"))
      (node (ref "R72") (pin "2") (pinfunction "2_2") (pintype "passive"))
    )
    (net (code "65") (name "/PCIE_PET0_N") (class "Default")
      (node (ref "C123") (pin "1") (pinfunction "1_1") (pintype "passive"))
    )
    (net (code "66") (name "/PCIE_PET0_P") (class "Default")
      (node (ref "C116") (pin "1") (pinfunction "1_1") (pintype "passive"))
    )
    (net (code "67") (name "/PCIE_REF_CLK_N") (class "Default")
      (node (ref "C111") (pin "1") (pinfunction "1_1") (pintype "passive"))
    )
    (net (code "68") (name "/PCIE_REF_CLK_P") (class "Default")
      (node (ref "C110") (pin "1") (pinfunction "1_1") (pintype "passive"))
    )
    (net (code "69") (name "/PCIE_W_DISABLE2#_LS") (class "Default")
      (node (ref "R76") (pin "1") (pinfunction "1_1") (pintype "passive"))
    )
    (net (code "70") (name "/R1_N") (class "Default")
      (node (ref "C123") (pin "2") (pinfunction "2_2") (pintype "passive"))
      (node (ref "IC6") (pin "R2") (pinfunction "SD1_RX_N_R2") (pintype "power_in"))
    )
    (net (code "71") (name "/R1_P") (class "Default")
      (node (ref "C116") (pin "2") (pinfunction "2_2") (pintype "passive"))
      (node (ref "IC6") (pin "P2") (pinfunction "SD1_RX_P_P2") (pintype "power_in"))
    )
    (net (code "72") (name "/T0_N") (class "Default")
      (node (ref "C114") (pin "2") (pinfunction "2_2") (pintype "passive"))
      (node (ref "IC6") (pin "R4") (pinfunction "SD1_TX_N_R4") (pintype "power_in"))
    )
    (net (code "73") (name "/T0_P") (class "Default")
      (node (ref "C112") (pin "2") (pinfunction "2_2") (pintype "passive"))
      (node (ref "IC6") (pin "P4") (pinfunction "SD1_TX_P_P4") (pintype "power_in"))
    )
    (net (code "74") (name "GND") (class "Default")
      (node (ref "C113") (pin "2") (pinfunction "2_2") (pintype "passive"))
      (node (ref "C115") (pin "2") (pinfunction "2_2") (pintype "passive"))
      (node (ref "C117") (pin "1") (pinfunction "1_1") (pintype "passive"))
      (node (ref "C118") (pin "1") (pinfunction "1_1") (pintype "passive"))
      (node (ref "C119") (pin "1") (pinfunction "1_1") (pintype "passive"))
      (node (ref "C120") (pin "1") (pinfunction "1_1") (pintype "passive"))
      (node (ref "C121") (pin "1") (pinfunction "1_1") (pintype "passive"))
      (node (ref "C122") (pin "2") (pinfunction "2_2") (pintype "passive"))
      (node (ref "C125") (pin "1") (pinfunction "1_1") (pintype "passive"))
      (node (ref "C126") (pin "2") (pinfunction "2_2") (pintype "passive"))
      (node (ref "C127") (pin "2") (pinfunction "2_2") (pintype "passive"))
      (node (ref "C128") (pin "1") (pinfunction "1_1") (pintype "passive"))
      (node (ref "C129") (pin "1") (pinfunction "1_1") (pintype "passive"))
      (node (ref "C131") (pin "1") (pinfunction "1_1") (pintype "passive"))
      (node (ref "C132") (pin "2") (pinfunction "2_2") (pintype "passive"))
      (node (ref "C133") (pin "2") (pinfunction "2_2") (pintype "passive"))
      (node (ref "C134") (pin "1") (pinfunction "1_1") (pintype "passive"))
      (node (ref "C135") (pin "1") (pinfunction "1_1") (pintype "passive"))
      (node (ref "C136") (pin "1") (pinfunction "1_1") (pintype "passive"))
      (node (ref "C137") (pin "1") (pinfunction "1_1") (pintype "passive"))
      (node (ref "C138") (pin "1") (pinfunction "1_1") (pintype "passive"))
      (node (ref "C139") (pin "1") (pinfunction "1_1") (pintype "passive"))
      (node (ref "C140") (pin "1") (pinfunction "1_1") (pintype "passive"))
      (node (ref "C141") (pin "1") (pinfunction "1_1") (pintype "passive"))
      (node (ref "C142") (pin "2") (pinfunction "2_2") (pintype "passive"))
      (node (ref "C143") (pin "1") (pinfunction "1_1") (pintype "passive"))
      (node (ref "C144") (pin "1") (pinfunction "1_1") (pintype "passive"))
      (node (ref "C145") (pin "1") (pinfunction "1_1") (pintype "passive"))
      (node (ref "C146") (pin "2") (pinfunction "2_2") (pintype "passive"))
      (node (ref "C147") (pin "1") (pinfunction "1_1") (pintype "passive"))
      (node (ref "C148") (pin "2") (pinfunction "2_2") (pintype "passive"))
      (node (ref "C149") (pin "2") (pinfunction "2_2") (pintype "passive"))
      (node (ref "C150") (pin "1") (pinfunction "1_1") (pintype "passive"))
      (node (ref "C151") (pin "1") (pinfunction "1_1") (pintype "passive"))
      (node (ref "C152") (pin "1") (pinfunction "1_1") (pintype "passive"))
      (node (ref "C153") (pin "1") (pinfunction "1_1") (pintype "passive"))
      (node (ref "C154") (pin "2") (pinfunction "2_2") (pintype "passive"))
      (node (ref "C155") (pin "1") (pinfunction "1_1") (pintype "passive"))
      (node (ref "C156") (pin "1") (pinfunction "1_1") (pintype "passive"))
      (node (ref "C157") (pin "1") (pinfunction "1_1") (pintype "passive"))
      (node (ref "C158") (pin "1") (pinfunction "1_1") (pintype "passive"))
      (node (ref "C159") (pin "1") (pinfunction "1_1") (pintype "passive"))
      (node (ref "C160") (pin "1") (pinfunction "1_1") (pintype "passive"))
      (node (ref "IC6") (pin "B1") (pinfunction "AFE_GND01_B1") (pintype "power_in"))
      (node (ref "IC6") (pin "B11") (pinfunction "AFE_GND04_B11") (pintype "power_in"))
      (node (ref "IC6") (pin "B13") (pinfunction "AFE_GND05_B13") (pintype "power_in"))
      (node (ref "IC6") (pin "B15") (pinfunction "AFE_GND06_B15") (pintype "power_in"))
      (node (ref "IC6") (pin "B3") (pinfunction "AFE_GND02_B3") (pintype "power_in"))
      (node (ref "IC6") (pin "B5") (pinfunction "AFE_GND03_B5") (pintype "power_in"))
      (node (ref "IC6") (pin "C10") (pinfunction "AFE_GND12_C10") (pintype "power_in"))
      (node (ref "IC6") (pin "C12") (pinfunction "AFE_GND13_C12") (pintype "power_in"))
      (node (ref "IC6") (pin "C14") (pinfunction "AFE_GND14_C14") (pintype "power_in"))
      (node (ref "IC6") (pin "C2") (pinfunction "AFE_GND07_C2") (pintype "power_in"))
      (node (ref "IC6") (pin "C4") (pinfunction "AFE_GND08_C4") (pintype "power_in"))
      (node (ref "IC6") (pin "C6") (pinfunction "AFE_GND09_C6") (pintype "power_in"))
      (node (ref "IC6") (pin "C7") (pinfunction "AFE_GND10_C7") (pintype "power_in"))
      (node (ref "IC6") (pin "C9") (pinfunction "AFE_GND11_C9") (pintype "power_in"))
      (node (ref "IC6") (pin "D10") (pinfunction "AFE_GND17_D10") (pintype "power_in"))
      (node (ref "IC6") (pin "D14") (pinfunction "AFE_GND18_D14") (pintype "power_in"))
      (node (ref "IC6") (pin "D2") (pinfunction "AFE_GND15_D2") (pintype "power_in"))
      (node (ref "IC6") (pin "D5") (pinfunction "VREF_RX_N_D5") (pintype "power_in"))
      (node (ref "IC6") (pin "D6") (pinfunction "AFE_GND16_D6") (pintype "power_in"))
      (node (ref "IC6") (pin "E1") (pinfunction "AFE_GND19_E1") (pintype "power_in"))
      (node (ref "IC6") (pin "E12") (pinfunction "AFE_GND23_E12") (pintype "power_in"))
      (node (ref "IC6") (pin "E15") (pinfunction "AFE_GND24_E15") (pintype "power_in"))
      (node (ref "IC6") (pin "E4") (pinfunction "AFE_GND20_E4") (pintype "power_in"))
      (node (ref "IC6") (pin "E7") (pinfunction "AFE_GND21_E7") (pintype "power_in"))
      (node (ref "IC6") (pin "E9") (pinfunction "AFE_GND22_E9") (pintype "power_in"))
      (node (ref "IC6") (pin "F12") (pinfunction "GND01_F12") (pintype "power_in"))
      (node (ref "IC6") (pin "F3") (pinfunction "AFE_GND25_F3") (pintype "power_in"))
      (node (ref "IC6") (pin "F4") (pinfunction "AFE_GND26_F4") (pintype "power_in"))
      (node (ref "IC6") (pin "F8") (pinfunction "AFE_GND27_F8") (pintype "power_in"))
      (node (ref "IC6") (pin "G11") (pinfunction "GND06_G11") (pintype "power_in"))
      (node (ref "IC6") (pin "G2") (pinfunction "AFE_GND28_G2") (pintype "power_in"))
      (node (ref "IC6") (pin "G3") (pinfunction "GND02_G3") (pintype "power_in"))
      (node (ref "IC6") (pin "G5") (pinfunction "GND03_G5") (pintype "power_in"))
      (node (ref "IC6") (pin "G7") (pinfunction "GND04_G7") (pintype "power_in"))
      (node (ref "IC6") (pin "G9") (pinfunction "GND05_G9") (pintype "power_in"))
      (node (ref "IC6") (pin "H1") (pinfunction "TD1_ANODE_H1") (pintype "power_in"))
      (node (ref "IC6") (pin "H12") (pinfunction "GND08_H12") (pintype "power_in"))
      (node (ref "IC6") (pin "H13") (pinfunction "LLCP_STIN_P_H13") (pintype "power_in"))
      (node (ref "IC6") (pin "H14") (pinfunction "LLCP_DIN_N_H14") (pintype "power_in"))
      (node (ref "IC6") (pin "H15") (pinfunction "LLCP_DIN_P_H15") (pintype "power_in"))
      (node (ref "IC6") (pin "H2") (pinfunction "TD1_CATHODE_H2") (pintype "power_in"))
      (node (ref "IC6") (pin "H8") (pinfunction "GND07_H8") (pintype "power_in"))
      (node (ref "IC6") (pin "J11") (pinfunction "GND14_J11") (pintype "power_in"))
      (node (ref "IC6") (pin "J13") (pinfunction "LLCP_STIN_N_J13") (pintype "power_in"))
      (node (ref "IC6") (pin "J2") (pinfunction "GND09_J2") (pintype "power_in"))
      (node (ref "IC6") (pin "J3") (pinfunction "GND10_J3") (pintype "power_in"))
      (node (ref "IC6") (pin "J5") (pinfunction "GND11_J5") (pintype "power_in"))
      (node (ref "IC6") (pin "J7") (pinfunction "GND12_J7") (pintype "power_in"))
      (node (ref "IC6") (pin "J9") (pinfunction "GND13_J9") (pintype "power_in"))
      (node (ref "IC6") (pin "K12") (pinfunction "GND16_K12") (pintype "power_in"))
      (node (ref "IC6") (pin "K2") (pinfunction "PROG_VDD_K2") (pintype "power_in"))
      (node (ref "IC6") (pin "K8") (pinfunction "GND15_K8") (pintype "power_in"))
      (node (ref "IC6") (pin "L1") (pinfunction "SD_GND1_L1") (pintype "power_in"))
      (node (ref "IC6") (pin "L11") (pinfunction "GND18_L11") (pintype "power_in"))
      (node (ref "IC6") (pin "L6") (pinfunction "SD_GND2_L6") (pintype "power_in"))
      (node (ref "IC6") (pin "L7") (pinfunction "SD_GND3_L7") (pintype "power_in"))
      (node (ref "IC6") (pin "L9") (pinfunction "GND17_L9") (pintype "power_in"))
      (node (ref "IC6") (pin "M2") (pinfunction "SD_GND4_M2") (pintype "power_in"))
      (node (ref "IC6") (pin "N2") (pinfunction "SD_GND5_N2") (pintype "power_in"))
      (node (ref "IC6") (pin "N4") (pinfunction "SD_GND6_N4") (pintype "power_in"))
      (node (ref "IC6") (pin "N6") (pinfunction "SD_GND7_N6") (pintype "power_in"))
      (node (ref "IC6") (pin "P1") (pinfunction "SD_GND8_P1") (pintype "power_in"))
      (node (ref "IC6") (pin "P3") (pinfunction "SD_GND9_P3") (pintype "power_in"))
      (node (ref "IC6") (pin "P5") (pinfunction "SD_GND10_P5") (pintype "power_in"))
      (node (ref "IC7") (pin "2") (pinfunction "GND_2") (pintype "passive"))
      (node (ref "R100") (pin "2") (pinfunction "2_2") (pintype "passive"))
      (node (ref "R101") (pin "2") (pinfunction "2_2") (pintype "passive"))
      (node (ref "R102") (pin "2") (pinfunction "2_2") (pintype "passive"))
      (node (ref "R103") (pin "2") (pinfunction "2_2") (pintype "passive"))
      (node (ref "R104") (pin "2") (pinfunction "2_2") (pintype "passive"))
      (node (ref "R105") (pin "2") (pinfunction "2_2") (pintype "passive"))
      (node (ref "R106") (pin "2") (pinfunction "2_2") (pintype "passive"))
      (node (ref "R107") (pin "2") (pinfunction "2_2") (pintype "passive"))
      (node (ref "R77") (pin "1") (pinfunction "1_1") (pintype "passive"))
      (node (ref "R85") (pin "2") (pinfunction "2_2") (pintype "passive"))
      (node (ref "R88") (pin "1") (pinfunction "1_1") (pintype "passive"))
      (node (ref "R99") (pin "2") (pinfunction "2_2") (pintype "passive"))
      (node (ref "X6") (pin "1") (pinfunction "1_1") (pintype "passive"))
      (node (ref "X6") (pin "12") (pinfunction "12_12") (pintype "passive"))
      (node (ref "X6") (pin "15") (pinfunction "15_15") (pintype "passive"))
      (node (ref "X6") (pin "4") (pinfunction "4_4") (pintype "passive"))
      (node (ref "X6") (pin "7") (pinfunction "7_7") (pintype "passive"))
      (node (ref "X6") (pin "9") (pinfunction "9_9") (pintype "passive"))
      (node (ref "X6") (pin "MP1") (pinfunction "MP1_MP1") (pintype "passive"))
      (node (ref "X6") (pin "MP2") (pinfunction "MP2_MP2") (pintype "passive"))
    )
    (net (code "75") (name "Net-(C124-Pad1)") (class "Default")
      (node (ref "C124") (pin "1") (pinfunction "1_1") (pintype "passive"))
      (node (ref "R82") (pin "1") (pinfunction "1_1") (pintype "passive"))
    )
    (net (code "76") (name "Net-(C130-Pad1)") (class "Default")
      (node (ref "C130") (pin "1") (pinfunction "1_1") (pintype "passive"))
      (node (ref "R86") (pin "1") (pinfunction "1_1") (pintype "passive"))
    )
    (net (code "77") (name "Net-(IC6A-CLKOUT)") (class "Default")
      (node (ref "IC6") (pin "N13") (pinfunction "CLKOUT_N13") (pintype "power_in"))
      (node (ref "R79") (pin "2") (pinfunction "2_2") (pintype "passive"))
    )
    (net (code "78") (name "Net-(IC6A-GPIO_19_{slash}ASLEEP)") (class "Default")
      (node (ref "IC6") (pin "R12") (pinfunction "GPIO_19_/ASLEEP_R12") (pintype "power_in"))
      (node (ref "R76") (pin "2") (pinfunction "2_2") (pintype "passive"))
    )
    (net (code "79") (name "Net-(IC6A-SCAN_MODE_B)") (class "Default")
      (node (ref "IC6") (pin "M13") (pinfunction "SCAN_MODE_B_M13") (pintype "power_in"))
      (node (ref "R87") (pin "1") (pinfunction "1_1") (pintype "passive"))
    )
    (net (code "80") (name "Net-(IC6A-SD1_IMP_CAL_RX)") (class "Default")
      (node (ref "IC6") (pin "K4") (pinfunction "SD1_IMP_CAL_RX_K4") (pintype "power_in"))
      (node (ref "R81") (pin "1") (pinfunction "1_1") (pintype "passive"))
    )
    (net (code "81") (name "Net-(IC6A-SD1_IMP_CAL_TX)") (class "Default")
      (node (ref "IC6") (pin "M4") (pinfunction "SD1_IMP_CAL_TX_M4") (pintype "power_in"))
      (node (ref "R80") (pin "1") (pinfunction "1_1") (pintype "passive"))
    )
    (net (code "82") (name "Net-(IC6B-IREF_TX)") (class "Default")
      (node (ref "IC6") (pin "E8") (pinfunction "IREF_TX_E8") (pintype "power_in"))
      (node (ref "R99") (pin "1") (pinfunction "1_1") (pintype "passive"))
    )
    (net (code "83") (name "Net-(IC7-D)") (class "Default")
      (node (ref "IC7") (pin "5") (pinfunction "D_5") (pintype "passive"))
      (node (ref "R78") (pin "1") (pinfunction "1_1") (pintype "passive"))
      (node (ref "R84") (pin "2") (pinfunction "2_2") (pintype "passive"))
      (node (ref "R85") (pin "1") (pinfunction "1_1") (pintype "passive"))
    )
    (net (code "84") (name "Net-(IC7-Y)") (class "Default")
      (node (ref "C124") (pin "2") (pinfunction "2_2") (pintype "passive"))
      (node (ref "IC7") (pin "4") (pinfunction "Y_4") (pintype "passive"))
      (node (ref "R77") (pin "2") (pinfunction "2_2") (pintype "passive"))
      (node (ref "R78") (pin "2") (pinfunction "2_2") (pintype "passive"))
    )
    (net (code "85") (name "Net-(IC7-Z)") (class "Default")
      (node (ref "C130") (pin "2") (pinfunction "2_2") (pintype "passive"))
      (node (ref "IC7") (pin "3") (pinfunction "Z_3") (pintype "passive"))
      (node (ref "R88") (pin "2") (pinfunction "2_2") (pintype "passive"))
    )
    (net (code "86") (name "Net-(J1-Pad6)") (class "Default")
      (node (ref "J1") (pin "6") (pinfunction "6_6") (pintype "passive"))
      (node (ref "R90") (pin "1") (pinfunction "1_1") (pintype "passive"))
    )
    (net (code "87") (name "Net-(R79-Pad1)") (class "Default")
      (node (ref "R79") (pin "1") (pinfunction "1_1") (pintype "passive"))
      (node (ref "TP1") (pin "1") (pintype "passive"))
    )
    (net (code "88") (name "VCC0P9") (class "Default")
      (node (ref "C137") (pin "2") (pinfunction "2_2") (pintype "passive"))
      (node (ref "C138") (pin "2") (pinfunction "2_2") (pintype "passive"))
      (node (ref "C139") (pin "2") (pinfunction "2_2") (pintype "passive"))
      (node (ref "C140") (pin "2") (pinfunction "2_2") (pintype "passive"))
      (node (ref "C141") (pin "2") (pinfunction "2_2") (pintype "passive"))
      (node (ref "C142") (pin "1") (pinfunction "1_1") (pintype "passive"))
      (node (ref "C146") (pin "1") (pinfunction "1_1") (pintype "passive"))
      (node (ref "C154") (pin "1") (pinfunction "1_1") (pintype "passive"))
      (node (ref "IC6") (pin "G10") (pinfunction "VDD2_G10") (pintype "power_in"))
      (node (ref "IC6") (pin "G6") (pinfunction "VDD1_G6") (pintype "power_in"))
      (node (ref "IC6") (pin "H11") (pinfunction "VDD6_H11") (pintype "power_in"))
      (node (ref "IC6") (pin "H5") (pinfunction "VDD3_H5") (pintype "power_in"))
      (node (ref "IC6") (pin "H7") (pinfunction "VDD4_H7") (pintype "power_in"))
      (node (ref "IC6") (pin "H9") (pinfunction "VDD5_H9") (pintype "power_in"))
      (node (ref "IC6") (pin "J10") (pinfunction "VDD8_J10") (pintype "power_in"))
      (node (ref "IC6") (pin "J6") (pinfunction "VDD7_J6") (pintype "power_in"))
    )
    (net (code "89") (name "VCC0P9_AFE_CVDD") (class "Default")
      (node (ref "C146") (pin "3") (pinfunction "3_3") (pintype "passive"))
      (node (ref "C150") (pin "2") (pinfunction "2_2") (pintype "passive"))
      (node (ref "C151") (pin "2") (pinfunction "2_2") (pintype "passive"))
      (node (ref "C152") (pin "2") (pinfunction "2_2") (pintype "passive"))
      (node (ref "C153") (pin "2") (pinfunction "2_2") (pintype "passive"))
      (node (ref "IC6") (pin "F11") (pinfunction "AFE_CVDD2_F11") (pintype "power_in"))
      (node (ref "IC6") (pin "F5") (pinfunction "AFE_CVDD1_F5") (pintype "power_in"))
    )
    (net (code "90") (name "VCC0P9_AFE_SVDD") (class "Default")
      (node (ref "C147") (pin "2") (pinfunction "2_2") (pintype "passive"))
      (node (ref "C148") (pin "1") (pinfunction "1_1") (pintype "passive"))
      (node (ref "C149") (pin "1") (pinfunction "1_1") (pintype "passive"))
      (node (ref "C154") (pin "3") (pinfunction "3_3") (pintype "passive"))
      (node (ref "C155") (pin "2") (pinfunction "2_2") (pintype "passive"))
      (node (ref "C156") (pin "2") (pinfunction "2_2") (pintype "passive"))
      (node (ref "C157") (pin "2") (pinfunction "2_2") (pintype "passive"))
      (node (ref "C158") (pin "2") (pinfunction "2_2") (pintype "passive"))
      (node (ref "C159") (pin "2") (pinfunction "2_2") (pintype "passive"))
      (node (ref "C160") (pin "2") (pinfunction "2_2") (pintype "passive"))
      (node (ref "IC6") (pin "D3") (pinfunction "VREF_RX_P_D3") (pintype "power_in"))
      (node (ref "IC6") (pin "E10") (pinfunction "AFE_SVDD2_E10") (pintype "power_in"))
      (node (ref "IC6") (pin "E6") (pinfunction "AFE_SVDD1_E6") (pintype "power_in"))
      (node (ref "IC6") (pin "F7") (pinfunction "AFE_SVDD3_F7") (pintype "power_in"))
      (node (ref "IC6") (pin "F9") (pinfunction "AFE_SVDD4_F9") (pintype "power_in"))
    )
    (net (code "91") (name "VCC0P9_SD_SVDD") (class "Default")
      (node (ref "C142") (pin "3") (pinfunction "3_3") (pintype "passive"))
      (node (ref "C143") (pin "2") (pinfunction "2_2") (pintype "passive"))
      (node (ref "C144") (pin "2") (pinfunction "2_2") (pintype "passive"))
      (node (ref "C145") (pin "2") (pinfunction "2_2") (pintype "passive"))
      (node (ref "IC6") (pin "K5") (pinfunction "SD_SVDD1_K5") (pintype "power_in"))
      (node (ref "IC6") (pin "K7") (pinfunction "SD_SVDD2_K7") (pintype "power_in"))
      (node (ref "R81") (pin "2") (pinfunction "2_2") (pintype "passive"))
    )
    (net (code "92") (name "VCC1P8") (class "Default")
      (node (ref "C128") (pin "2") (pinfunction "2_2") (pintype "passive"))
      (node (ref "C129") (pin "2") (pinfunction "2_2") (pintype "passive"))
      (node (ref "C133") (pin "1") (pinfunction "1_1") (pintype "passive"))
      (node (ref "IC6") (pin "K1") (pinfunction "TH_VDD_K1") (pintype "power_in"))
      (node (ref "IC6") (pin "K11") (pinfunction "OVDD2_K11") (pintype "power_in"))
      (node (ref "IC6") (pin "K9") (pinfunction "OVDD1_K9") (pintype "power_in"))
      (node (ref "IC6") (pin "L10") (pinfunction "OVDD3_L10") (pintype "power_in"))
      (node (ref "J1") (pin "4") (pinfunction "4_4") (pintype "passive"))
      (node (ref "R73") (pin "1") (pinfunction "1_1") (pintype "passive"))
      (node (ref "R74") (pin "1") (pinfunction "1_1") (pintype "passive"))
      (node (ref "R83") (pin "2") (pinfunction "2_2") (pintype "passive"))
      (node (ref "R87") (pin "2") (pinfunction "2_2") (pintype "passive"))
      (node (ref "R89") (pin "1") (pinfunction "1_1") (pintype "passive"))
    )
    (net (code "93") (name "VCC1P8_AFE_OTVDD") (class "Default")
      (node (ref "C133") (pin "3") (pinfunction "3_3") (pintype "passive"))
      (node (ref "C134") (pin "2") (pinfunction "2_2") (pintype "passive"))
      (node (ref "C135") (pin "2") (pinfunction "2_2") (pintype "passive"))
      (node (ref "C136") (pin "2") (pinfunction "2_2") (pintype "passive"))
      (node (ref "IC6") (pin "C8") (pinfunction "AFE_OTVDD_C8") (pintype "power_in"))
      (node (ref "IC6") (pin "D11") (pinfunction "AFE_OMVDD_D11") (pintype "power_in"))
    )
    (net (code "94") (name "VCC1P8_AVDD_PLAT") (class "Default")
      (node (ref "C125") (pin "2") (pinfunction "2_2") (pintype "passive"))
      (node (ref "C126") (pin "1") (pinfunction "1_1") (pintype "passive"))
      (node (ref "C127") (pin "1") (pinfunction "1_1") (pintype "passive"))
      (node (ref "IC6") (pin "H3") (pinfunction "AVDD_PLAT_H3") (pintype "power_in"))
      (node (ref "R83") (pin "1") (pinfunction "1_1") (pintype "passive"))
    )
    (net (code "95") (name "VCC1P35") (class "Default")
      (node (ref "C115") (pin "1") (pinfunction "1_1") (pintype "passive"))
      (node (ref "R75") (pin "2") (pinfunction "2_2") (pintype "passive"))
    )
    (net (code "96") (name "VCC1P35_AVDD_SD_PLL") (class "Default")
      (node (ref "C117") (pin "2") (pinfunction "2_2") (pintype "passive"))
      (node (ref "C118") (pin "2") (pinfunction "2_2") (pintype "passive"))
      (node (ref "C122") (pin "1") (pinfunction "1_1") (pintype "passive"))
      (node (ref "IC6") (pin "L3") (pinfunction "AVDD_SD_PLL_L3") (pintype "power_in"))
      (node (ref "R75") (pin "1") (pinfunction "1_1") (pintype "passive"))
    )
    (net (code "97") (name "VCC1P35_SD_XVDD") (class "Default")
      (node (ref "C115") (pin "3") (pinfunction "3_3") (pintype "passive"))
      (node (ref "C119") (pin "2") (pinfunction "2_2") (pintype "passive"))
      (node (ref "C120") (pin "2") (pinfunction "2_2") (pintype "passive"))
      (node (ref "C121") (pin "2") (pinfunction "2_2") (pintype "passive"))
      (node (ref "IC6") (pin "M5") (pinfunction "SD_XVDD1_M5") (pintype "power_in"))
      (node (ref "IC6") (pin "M6") (pinfunction "SD_XVDD2_M6") (pintype "power_in"))
      (node (ref "R80") (pin "2") (pinfunction "2_2") (pintype "passive"))
    )
    (net (code "98") (name "VCC3P3") (class "Default")
      (node (ref "X6") (pin "8") (pinfunction "8_8") (pintype "passive"))
    )
    (net (code "99") (name "VCC3P3_CLK") (class "Default")
      (node (ref "C131") (pin "2") (pinfunction "2_2") (pintype "passive"))
      (node (ref "C132") (pin "1") (pinfunction "1_1") (pintype "passive"))
      (node (ref "IC7") (pin "1") (pinfunction "VCC_1") (pintype "passive"))
    )
    (net (code "100") (name "VCC3P3_MPCIE") (class "Default")
      (node (ref "R72") (pin "1") (pinfunction "1_1") (pintype "passive"))
    )
    (net (code "101") (name "unconnected-(IC6B-LLCP_DOUT_N-PadG13)") (class "Default")
      (node (ref "IC6") (pin "G13") (pinfunction "LLCP_DOUT_N_G13") (pintype "power_in+no_connect"))
    )
    (net (code "102") (name "unconnected-(IC6B-LLCP_DOUT_P-PadF13)") (class "Default")
      (node (ref "IC6") (pin "F13") (pinfunction "LLCP_DOUT_P_F13") (pintype "power_in+no_connect"))
    )
    (net (code "103") (name "unconnected-(IC6B-LLCP_STOUT_N-PadF14)") (class "Default")
      (node (ref "IC6") (pin "F14") (pinfunction "LLCP_STOUT_N_F14") (pintype "power_in+no_connect"))
    )
    (net (code "104") (name "unconnected-(IC6B-LLCP_STOUT_P-PadF15)") (class "Default")
      (node (ref "IC6") (pin "F15") (pinfunction "LLCP_STOUT_P_F15") (pintype "power_in+no_connect"))
    )
    (net (code "105") (name "unconnected-(IC6B-TX_DET-PadD13)") (class "Default")
      (node (ref "IC6") (pin "D13") (pinfunction "TX_DET_D13") (pintype "power_in+no_connect"))
    )
  )
)
